# Controller_Peripheral_Iso.net
KiCad netlist of a schematic drawn in Altium Designer
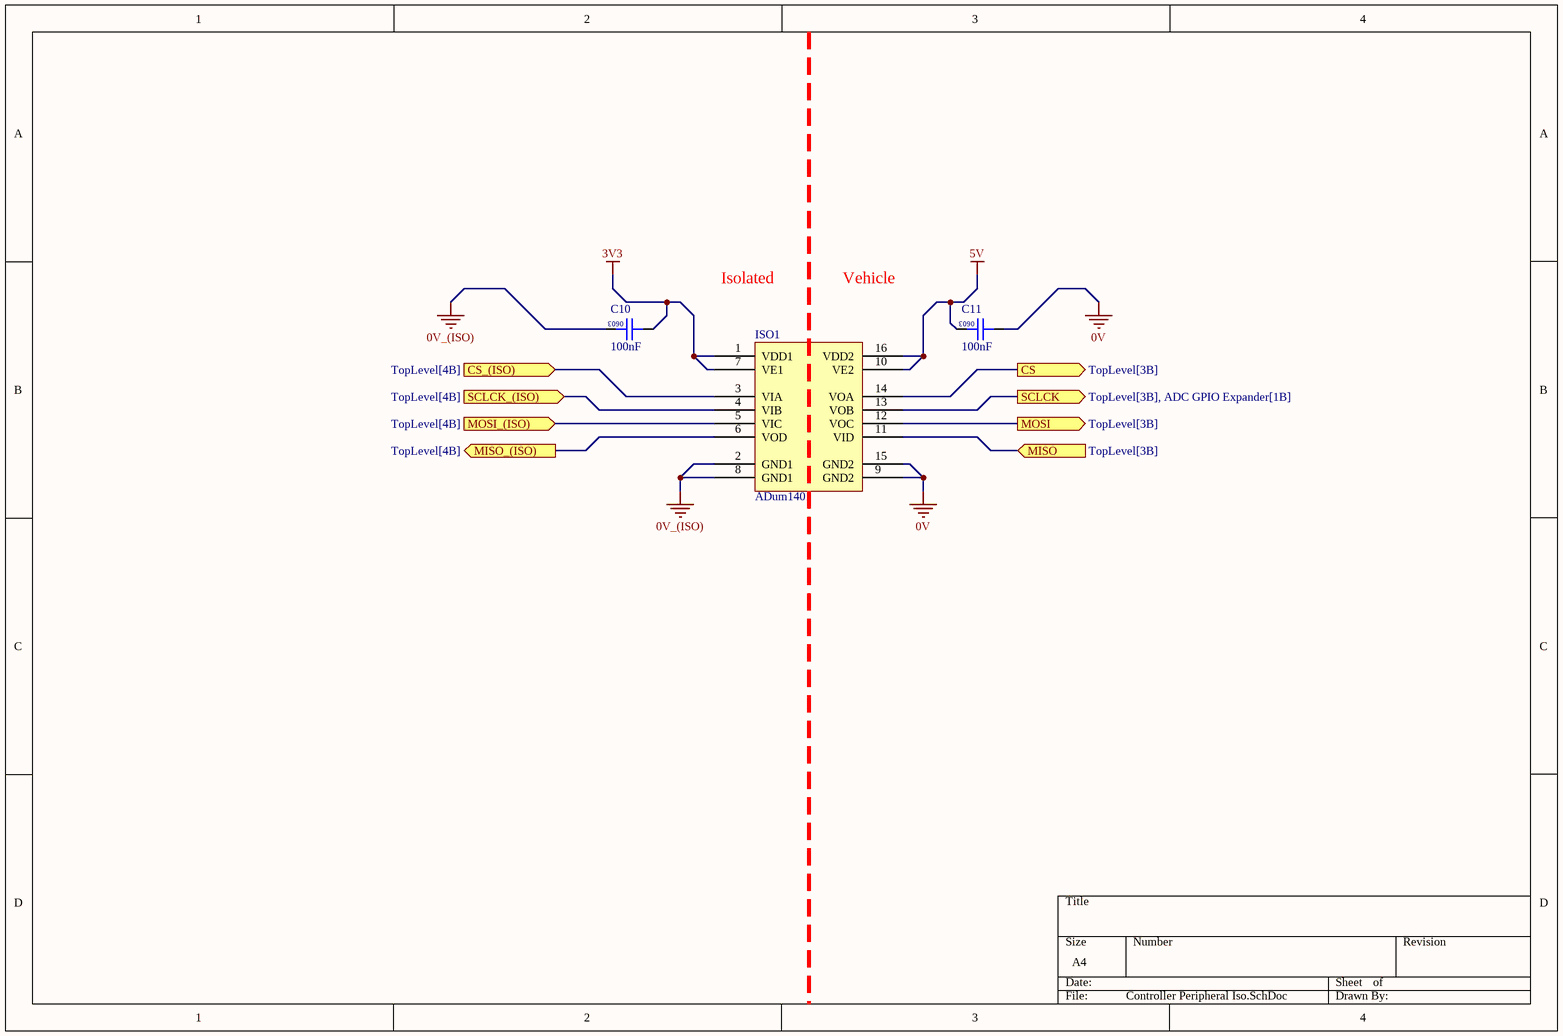
[diagram p0: Controller Peripheral Iso.SchDoc]

(export (version "E")
  (design (tool "Eeschema 10.0.6"))
  (components
    (comp (ref "C10")
      (value "100nF")
      (footprint "0603")
      (fields
        (field (name "PART NUMBER") "GCM188L81H104KA57D")
        (field (name "MANUFACTURER") "muRata")
        (field (name "TOLERANCE") "±10%")
      )
      (libsource (lib "ts_standard_library") (part "Capacitor 0603"))
    )
    (comp (ref "C11")
      (value "100nF")
      (footprint "0603")
      (fields
        (field (name "PART NUMBER") "GCM188L81H104KA57D")
        (field (name "MANUFACTURER") "muRata")
        (field (name "TOLERANCE") "±10%")
      )
      (libsource (lib "ts_standard_library") (part "Capacitor 0603"))
    )
    (comp (ref "ISO1")
      (value "ADum1401")
      (footprint "AD 16-SOIC")
      (fields (field (name "PART NUMBER") "ADuM1401") (field (name "MANUFACTURER") "Analog Devices"))
      (libsource (lib "ts_standard_library") (part "ADum1401"))
    )
  )
  (nets
    (net (code "1") (name "/CS") (class "Default")
      (node (ref "ISO1") (pin "14") (pinfunction "VOA_14") (pintype "passive"))
    )
    (net (code "2") (name "/CS_(ISO)") (class "Default")
      (node (ref "ISO1") (pin "3") (pinfunction "VIA_3") (pintype "passive"))
    )
    (net (code "3") (name "/MISO") (class "Default")
      (node (ref "ISO1") (pin "11") (pinfunction "VID_11") (pintype "passive"))
    )
    (net (code "4") (name "/MISO_(ISO)") (class "Default")
      (node (ref "ISO1") (pin "6") (pinfunction "VOD_6") (pintype "passive"))
    )
    (net (code "5") (name "/MOSI") (class "Default")
      (node (ref "ISO1") (pin "12") (pinfunction "VOC_12") (pintype "passive"))
    )
    (net (code "6") (name "/MOSI_(ISO)") (class "Default")
      (node (ref "ISO1") (pin "5") (pinfunction "VIC_5") (pintype "passive"))
    )
    (net (code "7") (name "/SCLCK") (class "Default")
      (node (ref "ISO1") (pin "13") (pinfunction "VOB_13") (pintype "passive"))
    )
    (net (code "8") (name "/SCLCK_(ISO)") (class "Default")
      (node (ref "ISO1") (pin "4") (pinfunction "VIB_4") (pintype "passive"))
    )
    (net (code "9") (name "0V") (class "Default")
      (node (ref "C11") (pin "1") (pinfunction "1_1") (pintype "passive"))
      (node (ref "ISO1") (pin "15") (pinfunction "GND2_15") (pintype "passive"))
      (node (ref "ISO1") (pin "9") (pinfunction "GND2_9") (pintype "passive"))
    )
    (net (code "10") (name "0V_(ISO)") (class "Default")
      (node (ref "C10") (pin "2") (pinfunction "2_2") (pintype "passive"))
      (node (ref "ISO1") (pin "2") (pinfunction "GND1_2") (pintype "passive"))
      (node (ref "ISO1") (pin "8") (pinfunction "GND1_8") (pintype "passive"))
    )
    (net (code "11") (name "3V3") (class "Default")
      (node (ref "C10") (pin "1") (pinfunction "1_1") (pintype "passive"))
      (node (ref "ISO1") (pin "1") (pinfunction "VDD1_1") (pintype "passive"))
      (node (ref "ISO1") (pin "7") (pinfunction "VE1_7") (pintype "passive"))
    )
    (net (code "12") (name "5V") (class "Default")
      (node (ref "C11") (pin "2") (pinfunction "2_2") (pintype "passive"))
      (node (ref "ISO1") (pin "10") (pinfunction "VE2_10") (pintype "passive"))
      (node (ref "ISO1") (pin "16") (pinfunction "VDD2_16") (pintype "passive"))
    )
  )
)
